# Sensors.net
KiCad netlist of a schematic drawn in Altium Designer
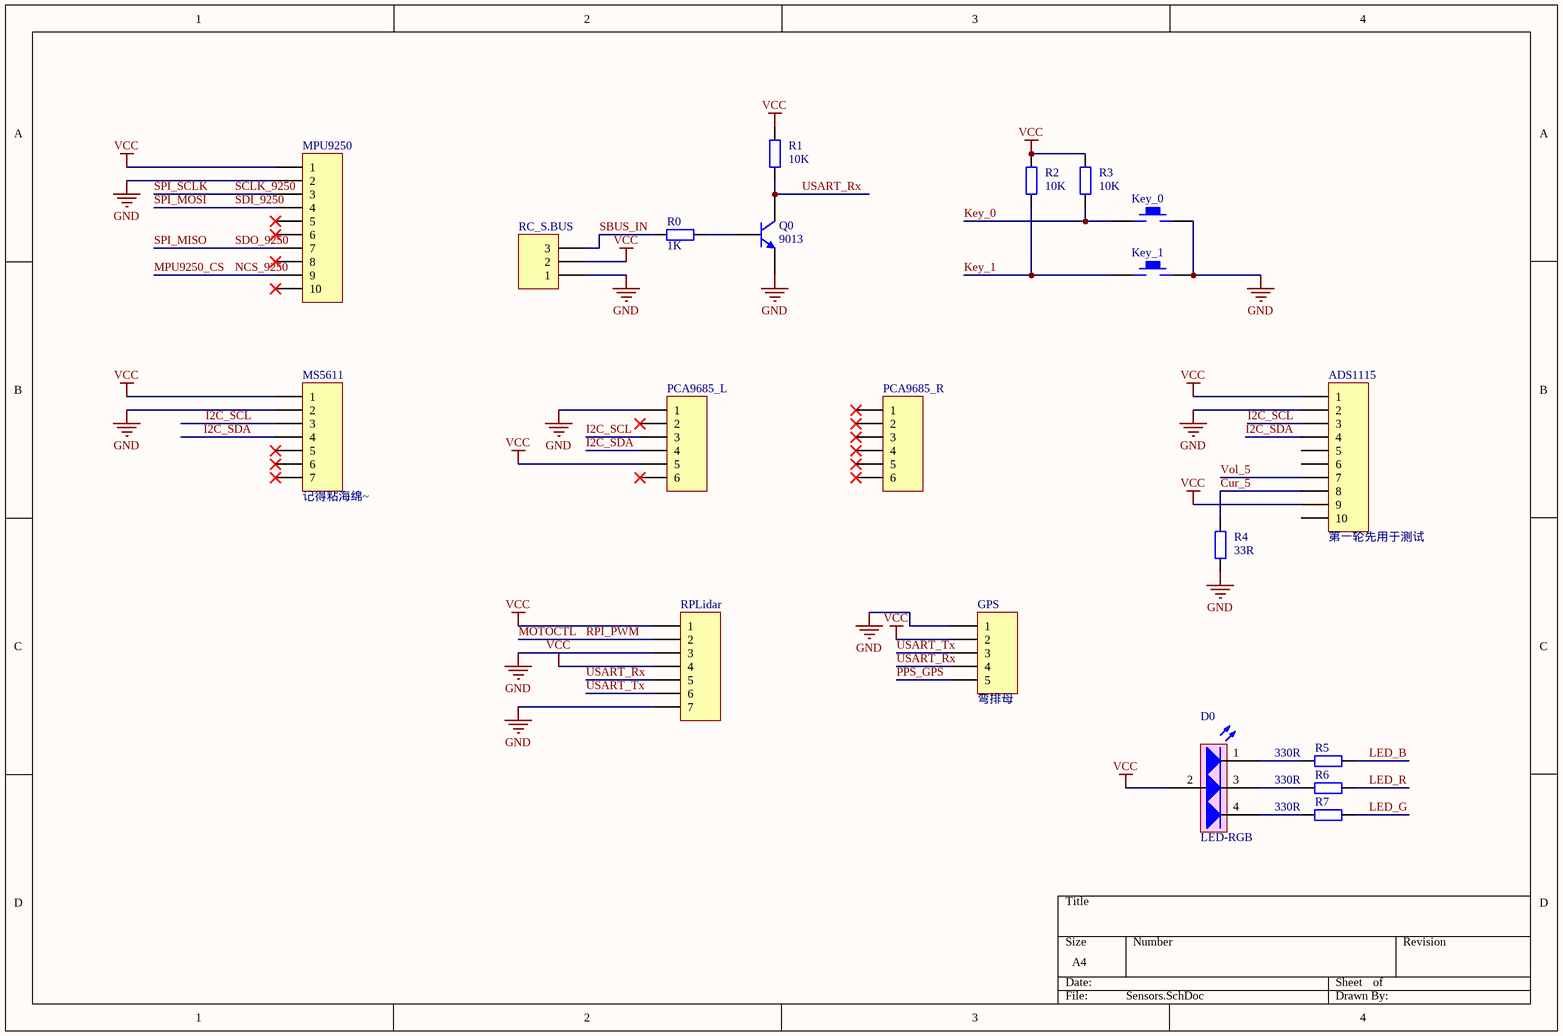
[diagram p0: Sensors.SchDoc]

(export (version "E")
  (design (tool "Eeschema 10.0.6"))
  (components
    (comp (ref "ADS1115")
      (value "第一轮先用于测试")
      (footprint "HDR1X10")
      (description "Header, 10-Pin")
      (fields (field (name "PUBLISHER") "Altium Limited"))
      (libsource (lib "Miscellaneous Connectors") (part "Header 10"))
    )
    (comp (ref "D0")
      (value "LED-RGB")
      (footprint "5050-ok:LED_5050_RGB")
      (description "三基色LED")
      (fields (field (name "PUBLISHER") "Altium Limited"))
      (libsource (lib "fszhang") (part "LED-RGB"))
    )
    (comp (ref "GPS")
      (value "弯排母")
      (footprint "HDR1X5")
      (description "Header, 5-Pin")
      (fields (field (name "PUBLISHER") "Altium Limited"))
      (libsource (lib "Miscellaneous Connectors") (part "Header 5"))
    )
    (comp (ref "Key_0")
      (value "~")
      (footprint "KEY_M")
      (libsource (lib "ATK-SIM900A GSM模块封装库") (part "KEY_M"))
    )
    (comp (ref "Key_1")
      (value "~")
      (footprint "KEY_M")
      (libsource (lib "ATK-SIM900A GSM模块封装库") (part "KEY_M"))
    )
    (comp (ref "MPU9250")
      (value "Header 10")
      (footprint "HDR1X10")
      (description "Header, 10-Pin")
      (fields (field (name "PUBLISHER") "Altium Limited"))
      (libsource (lib "Miscellaneous Connectors") (part "Header 10"))
    )
    (comp (ref "MS5611")
      (value "记得粘海绵~")
      (footprint "HDR1X7")
      (description "Header, 7-Pin")
      (fields (field (name "PUBLISHER") "Altium Limited"))
      (libsource (lib "Miscellaneous Connectors") (part "Header 7"))
    )
    (comp (ref "PCA9685_L")
      (value "Header 6")
      (footprint "HDR1X6")
      (description "Header, 6-Pin")
      (fields (field (name "PUBLISHER") "Altium Limited"))
      (libsource (lib "Miscellaneous Connectors") (part "Header 6"))
    )
    (comp (ref "PCA9685_R")
      (value "Header 6")
      (footprint "HDR1X6")
      (description "Header, 6-Pin")
      (fields (field (name "PUBLISHER") "Altium Limited"))
      (libsource (lib "Miscellaneous Connectors") (part "Header 6"))
    )
    (comp (ref "Q0")
      (value "9013")
      (footprint "Miscellaneous Devices:SOT23_L")
      (description "NPN General Purpose Amplifier")
      (fields (field (name "PUBLISHER") "Altium Limited"))
      (libsource (lib "Miscellaneous Devices") (part "2N3904"))
    )
    (comp (ref "R0")
      (value "1K")
      (footprint "3.5TFTLCD封装库:0805")
      (description "Resistor")
      (fields (field (name "Comment") "Res2") (field (name "PUBLISHER") "Altium Limited"))
      (libsource (lib "") (part "Res2_1"))
    )
    (comp (ref "R1")
      (value "10K")
      (footprint "3.5TFTLCD封装库:0805")
      (description "Resistor")
      (fields (field (name "Comment") "Res2") (field (name "PUBLISHER") "Altium Limited"))
      (libsource (lib "Miscellaneous Devices") (part "Res2"))
    )
    (comp (ref "R2")
      (value "10K")
      (footprint "3.5TFTLCD封装库:0805")
      (description "Resistor")
      (fields (field (name "Comment") "Res2") (field (name "PUBLISHER") "Altium Limited"))
      (libsource (lib "Miscellaneous Devices") (part "Res2"))
    )
    (comp (ref "R3")
      (value "10K")
      (footprint "3.5TFTLCD封装库:0805")
      (description "Resistor")
      (fields (field (name "Comment") "Res2") (field (name "PUBLISHER") "Altium Limited"))
      (libsource (lib "Miscellaneous Devices") (part "Res2"))
    )
    (comp (ref "R4")
      (value "33R")
      (footprint "3.5TFTLCD封装库:0805")
      (description "Resistor")
      (fields (field (name "Comment") "Res2") (field (name "PUBLISHER") "Altium Limited"))
      (libsource (lib "Miscellaneous Devices") (part "Res2"))
    )
    (comp (ref "R5")
      (value "330R")
      (footprint "3.5TFTLCD封装库:0805")
      (description "Resistor")
      (fields (field (name "Comment") "Res2") (field (name "PUBLISHER") "Altium Limited"))
      (libsource (lib "") (part "Res2_1"))
    )
    (comp (ref "R6")
      (value "330R")
      (footprint "3.5TFTLCD封装库:0805")
      (description "Resistor")
      (fields (field (name "Comment") "Res2") (field (name "PUBLISHER") "Altium Limited"))
      (libsource (lib "") (part "Res2_1"))
    )
    (comp (ref "R7")
      (value "330R")
      (footprint "3.5TFTLCD封装库:0805")
      (description "Resistor")
      (fields (field (name "Comment") "Res2") (field (name "PUBLISHER") "Altium Limited"))
      (libsource (lib "") (part "Res2_1"))
    )
    (comp (ref "RC_S.BUS")
      (value "Header 3")
      (footprint "HDR1X3")
      (description "Header, 3-Pin")
      (fields (field (name "PUBLISHER") "Altium Limited"))
      (libsource (lib "Miscellaneous Connectors") (part "Header 3"))
    )
    (comp (ref "RPLidar")
      (value "Header 7")
      (footprint "HDR1X7")
      (description "Header, 7-Pin")
      (fields (field (name "PUBLISHER") "Altium Limited"))
      (libsource (lib "Miscellaneous Connectors") (part "Header 7"))
    )
  )
  (nets
    (net (code "1") (name "/Cur_5") (class "Default")
      (node (ref "ADS1115") (pin "8") (pinfunction "8_8") (pintype "passive"))
      (node (ref "R4") (pin "2") (pinfunction "2_2") (pintype "passive"))
    )
    (net (code "2") (name "/I2C_SCL") (class "Default")
      (node (ref "ADS1115") (pin "3") (pinfunction "3_3") (pintype "passive"))
      (node (ref "MS5611") (pin "3") (pinfunction "3_3") (pintype "passive"))
      (node (ref "PCA9685_L") (pin "3") (pinfunction "3_3") (pintype "passive"))
    )
    (net (code "3") (name "/I2C_SDA") (class "Default")
      (node (ref "ADS1115") (pin "4") (pinfunction "4_4") (pintype "passive"))
      (node (ref "MS5611") (pin "4") (pinfunction "4_4") (pintype "passive"))
      (node (ref "PCA9685_L") (pin "4") (pinfunction "4_4") (pintype "passive"))
    )
    (net (code "4") (name "/Key_0") (class "Default")
      (node (ref "Key_0") (pin "1") (pinfunction "1_1") (pintype "passive"))
      (node (ref "R3") (pin "1") (pinfunction "1_1") (pintype "passive"))
    )
    (net (code "5") (name "/Key_1") (class "Default")
      (node (ref "Key_1") (pin "1") (pinfunction "1_1") (pintype "passive"))
      (node (ref "R2") (pin "1") (pinfunction "1_1") (pintype "passive"))
    )
    (net (code "6") (name "/LED_B") (class "Default")
      (node (ref "R5") (pin "1") (pinfunction "1_1") (pintype "passive"))
    )
    (net (code "7") (name "/LED_G") (class "Default")
      (node (ref "R7") (pin "1") (pinfunction "1_1") (pintype "passive"))
    )
    (net (code "8") (name "/LED_R") (class "Default")
      (node (ref "R6") (pin "1") (pinfunction "1_1") (pintype "passive"))
    )
    (net (code "9") (name "/MOTOCTL") (class "Default")
      (node (ref "RPLidar") (pin "2") (pinfunction "2_2") (pintype "passive"))
    )
    (net (code "10") (name "/MPU9250_CS") (class "Default")
      (node (ref "MPU9250") (pin "9") (pinfunction "9_9") (pintype "passive"))
    )
    (net (code "11") (name "/PPS_GPS") (class "Default")
      (node (ref "GPS") (pin "5") (pinfunction "5_5") (pintype "passive"))
    )
    (net (code "12") (name "/SBUS_IN") (class "Default")
      (node (ref "R0") (pin "2") (pinfunction "2_2") (pintype "passive"))
      (node (ref "RC_S.BUS") (pin "3") (pinfunction "3_3") (pintype "passive"))
    )
    (net (code "13") (name "/SCLK_9250") (class "Default")
      (node (ref "MPU9250") (pin "3") (pinfunction "3_3") (pintype "passive"))
    )
    (net (code "14") (name "/SDI_9250") (class "Default")
      (node (ref "MPU9250") (pin "4") (pinfunction "4_4") (pintype "passive"))
    )
    (net (code "15") (name "/SDO_9250") (class "Default")
      (node (ref "MPU9250") (pin "7") (pinfunction "7_7") (pintype "passive"))
    )
    (net (code "16") (name "/USART_Rx") (class "Default")
      (node (ref "GPS") (pin "4") (pinfunction "4_4") (pintype "passive"))
      (node (ref "Q0") (pin "1") (pinfunction "E_1") (pintype "passive"))
      (node (ref "R1") (pin "1") (pinfunction "1_1") (pintype "passive"))
      (node (ref "RPLidar") (pin "5") (pinfunction "5_5") (pintype "passive"))
    )
    (net (code "17") (name "/USART_Tx") (class "Default")
      (node (ref "GPS") (pin "3") (pinfunction "3_3") (pintype "passive"))
      (node (ref "RPLidar") (pin "6") (pinfunction "6_6") (pintype "passive"))
    )
    (net (code "18") (name "/Vol_5") (class "Default")
      (node (ref "ADS1115") (pin "7") (pinfunction "7_7") (pintype "passive"))
    )
    (net (code "19") (name "GND") (class "Default")
      (node (ref "ADS1115") (pin "2") (pinfunction "2_2") (pintype "passive"))
      (node (ref "GPS") (pin "1") (pinfunction "1_1") (pintype "passive"))
      (node (ref "Key_0") (pin "2") (pinfunction "2_2") (pintype "passive"))
      (node (ref "Key_1") (pin "2") (pinfunction "2_2") (pintype "passive"))
      (node (ref "MPU9250") (pin "2") (pinfunction "2_2") (pintype "passive"))
      (node (ref "MS5611") (pin "2") (pinfunction "2_2") (pintype "passive"))
      (node (ref "PCA9685_L") (pin "1") (pinfunction "1_1") (pintype "passive"))
      (node (ref "Q0") (pin "3") (pinfunction "C_3") (pintype "passive"))
      (node (ref "R4") (pin "1") (pinfunction "1_1") (pintype "passive"))
      (node (ref "RC_S.BUS") (pin "1") (pinfunction "1_1") (pintype "passive"))
      (node (ref "RPLidar") (pin "3") (pinfunction "3_3") (pintype "passive"))
      (node (ref "RPLidar") (pin "7") (pinfunction "7_7") (pintype "passive"))
    )
    (net (code "20") (name "Net-(D0-B)") (class "Default")
      (node (ref "D0") (pin "4") (pinfunction "B_4") (pintype "passive"))
      (node (ref "R7") (pin "2") (pinfunction "2_2") (pintype "passive"))
    )
    (net (code "21") (name "Net-(D0-G)") (class "Default")
      (node (ref "D0") (pin "3") (pinfunction "G_3") (pintype "passive"))
      (node (ref "R6") (pin "2") (pinfunction "2_2") (pintype "passive"))
    )
    (net (code "22") (name "Net-(D0-R)") (class "Default")
      (node (ref "D0") (pin "1") (pinfunction "R_1") (pintype "passive"))
      (node (ref "R5") (pin "2") (pinfunction "2_2") (pintype "passive"))
    )
    (net (code "23") (name "Net-(Q0-B)") (class "Default")
      (node (ref "Q0") (pin "2") (pinfunction "B_2") (pintype "passive"))
      (node (ref "R0") (pin "1") (pinfunction "1_1") (pintype "passive"))
    )
    (net (code "24") (name "VCC") (class "Default")
      (node (ref "ADS1115") (pin "1") (pinfunction "1_1") (pintype "passive"))
      (node (ref "ADS1115") (pin "9") (pinfunction "9_9") (pintype "passive"))
      (node (ref "D0") (pin "2") (pinfunction "A_2") (pintype "passive"))
      (node (ref "GPS") (pin "2") (pinfunction "2_2") (pintype "passive"))
      (node (ref "MPU9250") (pin "1") (pinfunction "1_1") (pintype "passive"))
      (node (ref "MS5611") (pin "1") (pinfunction "1_1") (pintype "passive"))
      (node (ref "PCA9685_L") (pin "5") (pinfunction "5_5") (pintype "passive"))
      (node (ref "R1") (pin "2") (pinfunction "2_2") (pintype "passive"))
      (node (ref "R2") (pin "2") (pinfunction "2_2") (pintype "passive"))
      (node (ref "R3") (pin "2") (pinfunction "2_2") (pintype "passive"))
      (node (ref "RC_S.BUS") (pin "2") (pinfunction "2_2") (pintype "passive"))
      (node (ref "RPLidar") (pin "1") (pinfunction "1_1") (pintype "passive"))
      (node (ref "RPLidar") (pin "4") (pinfunction "4_4") (pintype "passive"))
    )
    (net (code "25") (name "unconnected-(ADS1115-Pad5)") (class "Default")
      (node (ref "ADS1115") (pin "5") (pinfunction "5_5") (pintype "passive"))
    )
    (net (code "26") (name "unconnected-(ADS1115-Pad6)") (class "Default")
      (node (ref "ADS1115") (pin "6") (pinfunction "6_6") (pintype "passive"))
    )
    (net (code "27") (name "unconnected-(ADS1115-Pad10)") (class "Default")
      (node (ref "ADS1115") (pin "10") (pinfunction "10_10") (pintype "passive"))
    )
    (net (code "28") (name "unconnected-(MPU9250-Pad5)") (class "Default")
      (node (ref "MPU9250") (pin "5") (pinfunction "5_5") (pintype "passive+no_connect"))
    )
    (net (code "29") (name "unconnected-(MPU9250-Pad6)") (class "Default")
      (node (ref "MPU9250") (pin "6") (pinfunction "6_6") (pintype "passive+no_connect"))
    )
    (net (code "30") (name "unconnected-(MPU9250-Pad8)") (class "Default")
      (node (ref "MPU9250") (pin "8") (pinfunction "8_8") (pintype "passive+no_connect"))
    )
    (net (code "31") (name "unconnected-(MPU9250-Pad10)") (class "Default")
      (node (ref "MPU9250") (pin "10") (pinfunction "10_10") (pintype "passive+no_connect"))
    )
    (net (code "32") (name "unconnected-(MS5611-Pad5)") (class "Default")
      (node (ref "MS5611") (pin "5") (pinfunction "5_5") (pintype "passive+no_connect"))
    )
    (net (code "33") (name "unconnected-(MS5611-Pad6)") (class "Default")
      (node (ref "MS5611") (pin "6") (pinfunction "6_6") (pintype "passive+no_connect"))
    )
    (net (code "34") (name "unconnected-(MS5611-Pad7)") (class "Default")
      (node (ref "MS5611") (pin "7") (pinfunction "7_7") (pintype "passive+no_connect"))
    )
    (net (code "35") (name "unconnected-(PCA9685_L-Pad2)") (class "Default")
      (node (ref "PCA9685_L") (pin "2") (pinfunction "2_2") (pintype "passive+no_connect"))
    )
    (net (code "36") (name "unconnected-(PCA9685_L-Pad6)") (class "Default")
      (node (ref "PCA9685_L") (pin "6") (pinfunction "6_6") (pintype "passive+no_connect"))
    )
    (net (code "37") (name "unconnected-(PCA9685_R-Pad1)") (class "Default")
      (node (ref "PCA9685_R") (pin "1") (pinfunction "1_1") (pintype "passive+no_connect"))
    )
    (net (code "38") (name "unconnected-(PCA9685_R-Pad2)") (class "Default")
      (node (ref "PCA9685_R") (pin "2") (pinfunction "2_2") (pintype "passive+no_connect"))
    )
    (net (code "39") (name "unconnected-(PCA9685_R-Pad3)") (class "Default")
      (node (ref "PCA9685_R") (pin "3") (pinfunction "3_3") (pintype "passive+no_connect"))
    )
    (net (code "40") (name "unconnected-(PCA9685_R-Pad4)") (class "Default")
      (node (ref "PCA9685_R") (pin "4") (pinfunction "4_4") (pintype "passive+no_connect"))
    )
    (net (code "41") (name "unconnected-(PCA9685_R-Pad5)") (class "Default")
      (node (ref "PCA9685_R") (pin "5") (pinfunction "5_5") (pintype "passive+no_connect"))
    )
    (net (code "42") (name "unconnected-(PCA9685_R-Pad6)") (class "Default")
      (node (ref "PCA9685_R") (pin "6") (pinfunction "6_6") (pintype "passive+no_connect"))
    )
  )
)
